# USB_UART.net
KiCad netlist of a schematic drawn in Altium Designer
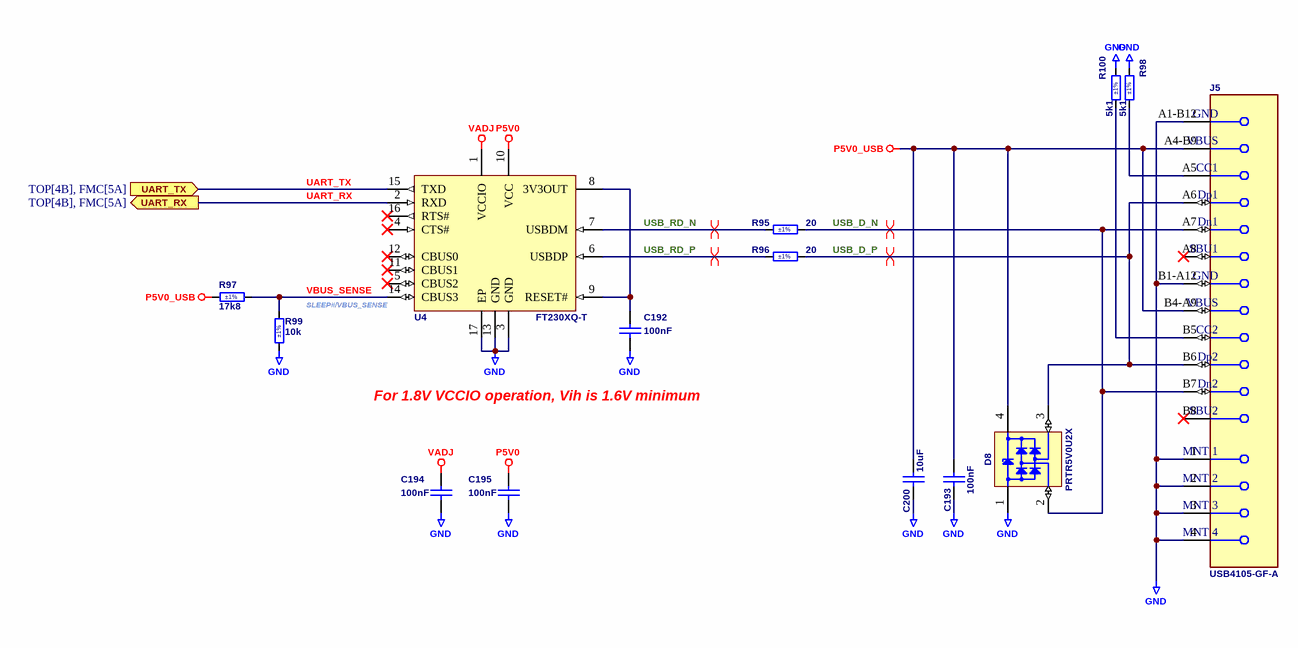
[diagram p0: USB_UART.SchDoc]

(export (version "E")
  (design (tool "Eeschema 10.0.6"))
  (components
    (comp (ref "C192")
      (value "100nF")
      (footprint "CAPC1005X55N")
      (description "Non-polarised capacitor")
      (fields
        (field (name "PART NUMBER") "CC0402_100NF_50V_10%_X7R")
        (field (name "VOLTAGE") "50V")
        (field (name "AUTHOR") "CERN DEM MR")
      )
      (libsource (lib "Capacitors") (part "Capacitor - non polarized"))
    )
    (comp (ref "C193")
      (value "100nF")
      (footprint "CAPC1005X55N")
      (description "Non-polarised capacitor")
      (fields
        (field (name "PART NUMBER") "CC0402_100NF_16V_10%_X7R")
        (field (name "VOLTAGE") "16V")
        (field (name "AUTHOR") "CERN DEM JLC")
      )
      (libsource (lib "Capacitors") (part "Capacitor - non polarized"))
    )
    (comp (ref "C194")
      (value "100nF")
      (footprint "CAPC1005X55N")
      (description "Non-polarised capacitor")
      (fields
        (field (name "PART NUMBER") "CC0402_100NF_50V_10%_X7R")
        (field (name "VOLTAGE") "50V")
        (field (name "AUTHOR") "CERN DEM MR")
      )
      (libsource (lib "Capacitors") (part "Capacitor - non polarized"))
    )
    (comp (ref "C195")
      (value "100nF")
      (footprint "CAPC1005X55N")
      (description "Non-polarised capacitor")
      (fields
        (field (name "PART NUMBER") "CC0402_100NF_50V_10%_X7R")
        (field (name "VOLTAGE") "50V")
        (field (name "AUTHOR") "CERN DEM MR")
      )
      (libsource (lib "Capacitors") (part "Capacitor - non polarized"))
    )
    (comp (ref "C200")
      (value "10uF")
      (footprint "CAPC1608X90N")
      (description "Non-polarised capacitor")
      (fields
        (field (name "PART NUMBER") "CC0603_10UF_16V_10%_X5R_MURATA_GRT188R61C106KE13")
        (field (name "VOLTAGE") "16V")
        (field (name "AUTHOR") "CERN DEM HF")
      )
      (libsource (lib "Capacitors") (part "Capacitor - non polarized"))
    )
    (comp (ref "D8")
      (value "PRTR5V0U2X")
      (footprint "SOT190P230X110-4N")
      (description "Ultra Low Capacitance Double Rail-to-Rail ESD Protection Diode")
      (fields
        (field (name "VOLTAGE") "5.5V")
        (field (name "MANUFACTURER") "NXP SEMICONDUCTORS")
        (field (name "AUTHOR") "CERN DEM JLC")
      )
      (libsource (lib "ICs And Semiconductors") (part "PRTR5V0U2X"))
    )
    (comp (ref "J5")
      (value "USB4105-GF-A")
      (footprint "FP-USB4105-GF-A-MFG")
      (description "CONN RCPT USB2.0 TYPEC 5A")
      (fields
        (field (name "MANUFACTURER") "GCT")
        (field (name "OCTOPART") "https://octopart.com/usb4105-gf-a-gct-106627878")
      )
      (libsource (lib "Connectors") (part "e7c17a616881a82b79941196b4bec10"))
    )
    (comp (ref "R95")
      (value "20")
      (footprint "RESC1005X40N")
      (description "Resistor - 1%")
      (fields
        (field (name "TOLERANCE") "±1%")
        (field (name "PART NUMBER") "R0402_20R_1%_0.0625W_100PPM")
        (field (name "POWER") "0.0625W")
        (field (name "AUTHOR") "CERN DEM JLC")
      )
      (libsource (lib "Resistors") (part "Resistor - 1%"))
    )
    (comp (ref "R96")
      (value "20")
      (footprint "RESC1005X40N")
      (description "Resistor - 1%")
      (fields
        (field (name "TOLERANCE") "±1%")
        (field (name "PART NUMBER") "R0402_20R_1%_0.0625W_100PPM")
        (field (name "POWER") "0.0625W")
        (field (name "AUTHOR") "CERN DEM JLC")
      )
      (libsource (lib "Resistors") (part "Resistor - 1%"))
    )
    (comp (ref "R97")
      (value "17k8")
      (footprint "RESC1005X40N")
      (description "Resistor - 1%")
      (fields
        (field (name "TOLERANCE") "±1%")
        (field (name "PART NUMBER") "R0402_17K8_1%_0.0625W_100PPM")
        (field (name "POWER") "0.0625W")
        (field (name "AUTHOR") "CERN DEM BC")
      )
      (libsource (lib "Resistors") (part "Resistor - 1%"))
    )
    (comp (ref "R98")
      (value "5k1")
      (footprint "RESC1005X40N")
      (description "Resistor - 1%")
      (fields
        (field (name "TOLERANCE") "±1%")
        (field (name "PART NUMBER") "R0402_5K1_1%_0.0625W_100PPM")
        (field (name "POWER") "0.0625W")
        (field (name "AUTHOR") "CERN DEM JLC")
      )
      (libsource (lib "Resistors") (part "Resistor - 1%"))
    )
    (comp (ref "R99")
      (value "10k")
      (footprint "RESC1005X40N")
      (description "Resistor - 1%")
      (fields
        (field (name "TOLERANCE") "±1%")
        (field (name "PART NUMBER") "R0402_10K_1%_0.0625W_100PPM")
        (field (name "POWER") "0.0625W")
        (field (name "AUTHOR") "CERN DEM JLC")
      )
      (libsource (lib "Resistors") (part "Resistor - 1%"))
    )
    (comp (ref "R100")
      (value "5k1")
      (footprint "RESC1005X40N")
      (description "Resistor - 1%")
      (fields
        (field (name "TOLERANCE") "±1%")
        (field (name "PART NUMBER") "R0402_5K1_1%_0.0625W_100PPM")
        (field (name "POWER") "0.0625W")
        (field (name "AUTHOR") "CERN DEM JLC")
      )
      (libsource (lib "Resistors") (part "Resistor - 1%"))
    )
    (comp (ref "U4")
      (value "FT230XQ-T")
      (footprint "QFN50P400X400X80_HS-17N")
      (fields (field (name "MANUFACTURER") "FTDI"))
      (libsource (lib "FTDI FT-X Series") (part "FT230XQ-T"))
    )
  )
  (nets
    (net (code "1") (name "/UART_RX") (class "Default")
      (node (ref "U4") (pin "2") (pinfunction "RXD_2") (pintype "input"))
    )
    (net (code "2") (name "/UART_TX") (class "Default")
      (node (ref "U4") (pin "15") (pinfunction "TXD_15") (pintype "output"))
    )
    (net (code "3") (name "/USB_D_N") (class "Default")
      (node (ref "D8") (pin "2") (pinfunction "I/O1_2") (pintype "bidirectional"))
      (node (ref "J5") (pin "A7") (pinfunction "Dn1_A7") (pintype "bidirectional"))
      (node (ref "J5") (pin "B7") (pinfunction "Dn2_B7") (pintype "bidirectional"))
      (node (ref "R95") (pin "2") (pinfunction "2_2") (pintype "passive"))
    )
    (net (code "4") (name "/USB_D_P") (class "Default")
      (node (ref "D8") (pin "3") (pinfunction "I/O2_3") (pintype "bidirectional"))
      (node (ref "J5") (pin "A6") (pinfunction "Dp1_A6") (pintype "bidirectional"))
      (node (ref "J5") (pin "B6") (pinfunction "Dp2_B6") (pintype "bidirectional"))
      (node (ref "R96") (pin "2") (pinfunction "2_2") (pintype "passive"))
    )
    (net (code "5") (name "/USB_RD_N") (class "Default")
      (node (ref "R95") (pin "1") (pinfunction "1_1") (pintype "passive"))
      (node (ref "U4") (pin "7") (pinfunction "USBDM_7") (pintype "input"))
    )
    (net (code "6") (name "/USB_RD_P") (class "Default")
      (node (ref "R96") (pin "1") (pinfunction "1_1") (pintype "passive"))
      (node (ref "U4") (pin "6") (pinfunction "USBDP_6") (pintype "input"))
    )
    (net (code "7") (name "/VBUS_SENSE") (class "Default")
      (node (ref "R97") (pin "2") (pinfunction "2_2") (pintype "passive"))
      (node (ref "R99") (pin "2") (pinfunction "2_2") (pintype "passive"))
      (node (ref "U4") (pin "14") (pinfunction "CBUS3_14") (pintype "bidirectional"))
    )
    (net (code "8") (name "GND") (class "Default")
      (node (ref "C192") (pin "1") (pinfunction "1_1") (pintype "passive"))
      (node (ref "C193") (pin "1") (pinfunction "1_1") (pintype "passive"))
      (node (ref "C194") (pin "1") (pinfunction "1_1") (pintype "passive"))
      (node (ref "C195") (pin "1") (pinfunction "1_1") (pintype "passive"))
      (node (ref "C200") (pin "1") (pinfunction "1_1") (pintype "passive"))
      (node (ref "D8") (pin "1") (pinfunction "GND_1") (pintype "power_in"))
      (node (ref "J5") (pin "1") (pinfunction "MNT_1_1") (pintype "power_in"))
      (node (ref "J5") (pin "2") (pinfunction "MNT_2_2") (pintype "power_in"))
      (node (ref "J5") (pin "3") (pinfunction "MNT_3_3") (pintype "power_in"))
      (node (ref "J5") (pin "4") (pinfunction "MNT_4_4") (pintype "power_in"))
      (node (ref "J5") (pin "A1-B12") (pinfunction "GND_A1-B12") (pintype "power_in"))
      (node (ref "J5") (pin "B1-A12") (pinfunction "GND_B1-A12") (pintype "bidirectional"))
      (node (ref "R100") (pin "2") (pinfunction "2_2") (pintype "passive"))
      (node (ref "R98") (pin "2") (pinfunction "2_2") (pintype "passive"))
      (node (ref "R99") (pin "1") (pinfunction "1_1") (pintype "passive"))
      (node (ref "U4") (pin "13") (pinfunction "GND_13") (pintype "power_in"))
      (node (ref "U4") (pin "17") (pinfunction "EP_17") (pintype "power_in"))
      (node (ref "U4") (pin "3") (pinfunction "GND_3") (pintype "power_in"))
    )
    (net (code "9") (name "Net-(J5-CC1)") (class "Default")
      (node (ref "J5") (pin "A5") (pinfunction "CC1_A5") (pintype "power_in"))
      (node (ref "R98") (pin "1") (pinfunction "1_1") (pintype "passive"))
    )
    (net (code "10") (name "Net-(J5-CC2)") (class "Default")
      (node (ref "J5") (pin "B5") (pinfunction "CC2_B5") (pintype "bidirectional"))
      (node (ref "R100") (pin "1") (pinfunction "1_1") (pintype "passive"))
    )
    (net (code "11") (name "Net-(U4-3V3OUT)") (class "Default")
      (node (ref "C192") (pin "2") (pinfunction "2_2") (pintype "passive"))
      (node (ref "U4") (pin "8") (pinfunction "3V3OUT_8") (pintype "power_in"))
      (node (ref "U4") (pin "9") (pinfunction "RESET#_9") (pintype "input"))
    )
    (net (code "12") (name "P5V0") (class "Default")
      (node (ref "C195") (pin "2") (pinfunction "2_2") (pintype "passive"))
      (node (ref "U4") (pin "10") (pinfunction "VCC_10") (pintype "power_in"))
    )
    (net (code "13") (name "P5V0_USB") (class "Default")
      (node (ref "C193") (pin "2") (pinfunction "2_2") (pintype "passive"))
      (node (ref "C200") (pin "2") (pinfunction "2_2") (pintype "passive"))
      (node (ref "D8") (pin "4") (pinfunction "VCC_4") (pintype "power_in"))
      (node (ref "J5") (pin "A4-B9") (pinfunction "VBUS_A4-B9") (pintype "power_in"))
      (node (ref "J5") (pin "B4-A9") (pinfunction "VBUS_B4-A9") (pintype "bidirectional"))
      (node (ref "R97") (pin "1") (pinfunction "1_1") (pintype "passive"))
    )
    (net (code "14") (name "VADJ") (class "Default")
      (node (ref "C194") (pin "2") (pinfunction "2_2") (pintype "passive"))
      (node (ref "U4") (pin "1") (pinfunction "VCCIO_1") (pintype "power_in"))
    )
    (net (code "15") (name "unconnected-(J5-SBU1-PadA8)") (class "Default")
      (node (ref "J5") (pin "A8") (pinfunction "SBU1_A8") (pintype "bidirectional+no_connect"))
    )
    (net (code "16") (name "unconnected-(J5-SBU2-PadB8)") (class "Default")
      (node (ref "J5") (pin "B8") (pinfunction "SBU2_B8") (pintype "power_in+no_connect"))
    )
    (net (code "17") (name "unconnected-(U4-CBUS0-Pad12)") (class "Default")
      (node (ref "U4") (pin "12") (pinfunction "CBUS0_12") (pintype "bidirectional+no_connect"))
    )
    (net (code "18") (name "unconnected-(U4-CBUS1-Pad11)") (class "Default")
      (node (ref "U4") (pin "11") (pinfunction "CBUS1_11") (pintype "bidirectional+no_connect"))
    )
    (net (code "19") (name "unconnected-(U4-CBUS2-Pad5)") (class "Default")
      (node (ref "U4") (pin "5") (pinfunction "CBUS2_5") (pintype "bidirectional+no_connect"))
    )
    (net (code "20") (name "unconnected-(U4-CTS#-Pad4)") (class "Default")
      (node (ref "U4") (pin "4") (pinfunction "CTS#_4") (pintype "input+no_connect"))
    )
    (net (code "21") (name "unconnected-(U4-RTS#-Pad16)") (class "Default")
      (node (ref "U4") (pin "16") (pinfunction "RTS#_16") (pintype "output+no_connect"))
    )
  )
)
